# Receiver.net
KiCad netlist of a schematic drawn in EAGLE
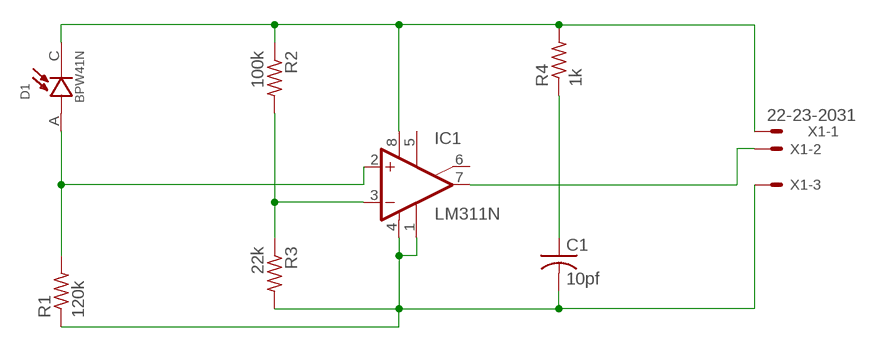
[diagram p0: schematic, sheet 1]

(export (version "E")
  (design (tool "Eeschema 10.0.6"))
  (components
    (comp (ref "C1")
      (value "10pf")
      (footprint "eagle-import:C025-024X044")
      (libsource (lib "eagle-import") (part "C-US025-024X044"))
    )
    (comp (ref "D1")
      (value "BPW41N")
      (footprint "eagle-import:DIO_BPW41N")
      (fields (field (name "MF") "Vishay Semiconductor Opto Division"))
      (libsource (lib "eagle-import") (part "BPW41N"))
    )
    (comp (ref "IC1")
      (value "LM311N")
      (footprint "eagle-import:DIL08")
      (libsource (lib "eagle-import") (part "LM311N"))
    )
    (comp (ref "R1")
      (value "120k")
      (footprint "eagle-import:0204_5")
      (libsource (lib "eagle-import") (part "R-US_0204/5"))
    )
    (comp (ref "R2")
      (value "100k")
      (footprint "eagle-import:0204_5")
      (libsource (lib "eagle-import") (part "R-US_0204/5"))
    )
    (comp (ref "R3")
      (value "22k")
      (footprint "eagle-import:0204_5")
      (libsource (lib "eagle-import") (part "R-US_0204/5"))
    )
    (comp (ref "R4")
      (value "1k")
      (footprint "eagle-import:0204_5")
      (libsource (lib "eagle-import") (part "R-US_0204/5"))
    )
    (comp (ref "X1")
      (value "22-23-2031")
      (footprint "eagle-import:22-23-2031")
      (fields (field (name "MF") "MOLEX"))
      (libsource (lib "eagle-import") (part "22-23-2031"))
    )
  )
  (nets
    (net (code "1") (name "Net-(C1-Pad1)") (class "Default")
      (node (ref "C1") (pin "1") (pinfunction "1_1") (pintype "passive"))
      (node (ref "R4") (pin "1") (pinfunction "1_1") (pintype "passive"))
    )
    (net (code "2") (name "Net-(IC1-+IN)") (class "Default")
      (node (ref "D1") (pin "A") (pinfunction "A_A") (pintype "passive"))
      (node (ref "IC1") (pin "2") (pinfunction "+IN_2") (pintype "input"))
      (node (ref "R1") (pin "2") (pinfunction "2_2") (pintype "passive"))
    )
    (net (code "3") (name "Net-(IC1--IN)") (class "Default")
      (node (ref "IC1") (pin "3") (pinfunction "-IN_3") (pintype "input"))
      (node (ref "R2") (pin "2") (pinfunction "2_2") (pintype "passive"))
      (node (ref "R3") (pin "1") (pinfunction "1_1") (pintype "passive"))
    )
    (net (code "4") (name "Net-(IC1-GND)") (class "Default")
      (node (ref "C1") (pin "2") (pinfunction "2_2") (pintype "passive"))
      (node (ref "IC1") (pin "1") (pinfunction "GND_1") (pintype "passive"))
      (node (ref "IC1") (pin "4") (pinfunction "V-_4") (pintype "power_in"))
      (node (ref "R1") (pin "1") (pinfunction "1_1") (pintype "passive"))
      (node (ref "R3") (pin "2") (pinfunction "2_2") (pintype "passive"))
      (node (ref "X1") (pin "3") (pinfunction "S_3") (pintype "passive"))
    )
    (net (code "5") (name "Net-(IC1-OUT)") (class "Default")
      (node (ref "IC1") (pin "7") (pinfunction "OUT_7") (pintype "output"))
      (node (ref "X1") (pin "2") (pinfunction "S_2") (pintype "passive"))
    )
    (net (code "6") (name "Net-(IC1-V+)") (class "Default")
      (node (ref "D1") (pin "C") (pinfunction "C_C") (pintype "passive"))
      (node (ref "IC1") (pin "8") (pinfunction "V+_8") (pintype "power_in"))
      (node (ref "R2") (pin "1") (pinfunction "1_1") (pintype "passive"))
      (node (ref "R4") (pin "2") (pinfunction "2_2") (pintype "passive"))
      (node (ref "X1") (pin "1") (pinfunction "S_1") (pintype "passive"))
    )
    (net (code "7") (name "unconnected-(IC1-ON-Pad5)") (class "Default")
      (node (ref "IC1") (pin "5") (pinfunction "ON_5") (pintype "passive"))
    )
    (net (code "8") (name "unconnected-(IC1-ON{slash}STR-Pad6)") (class "Default")
      (node (ref "IC1") (pin "6") (pinfunction "ON/STR_6") (pintype "passive"))
    )
  )
)
